# pH.net
KiCad netlist of a schematic drawn in EAGLE
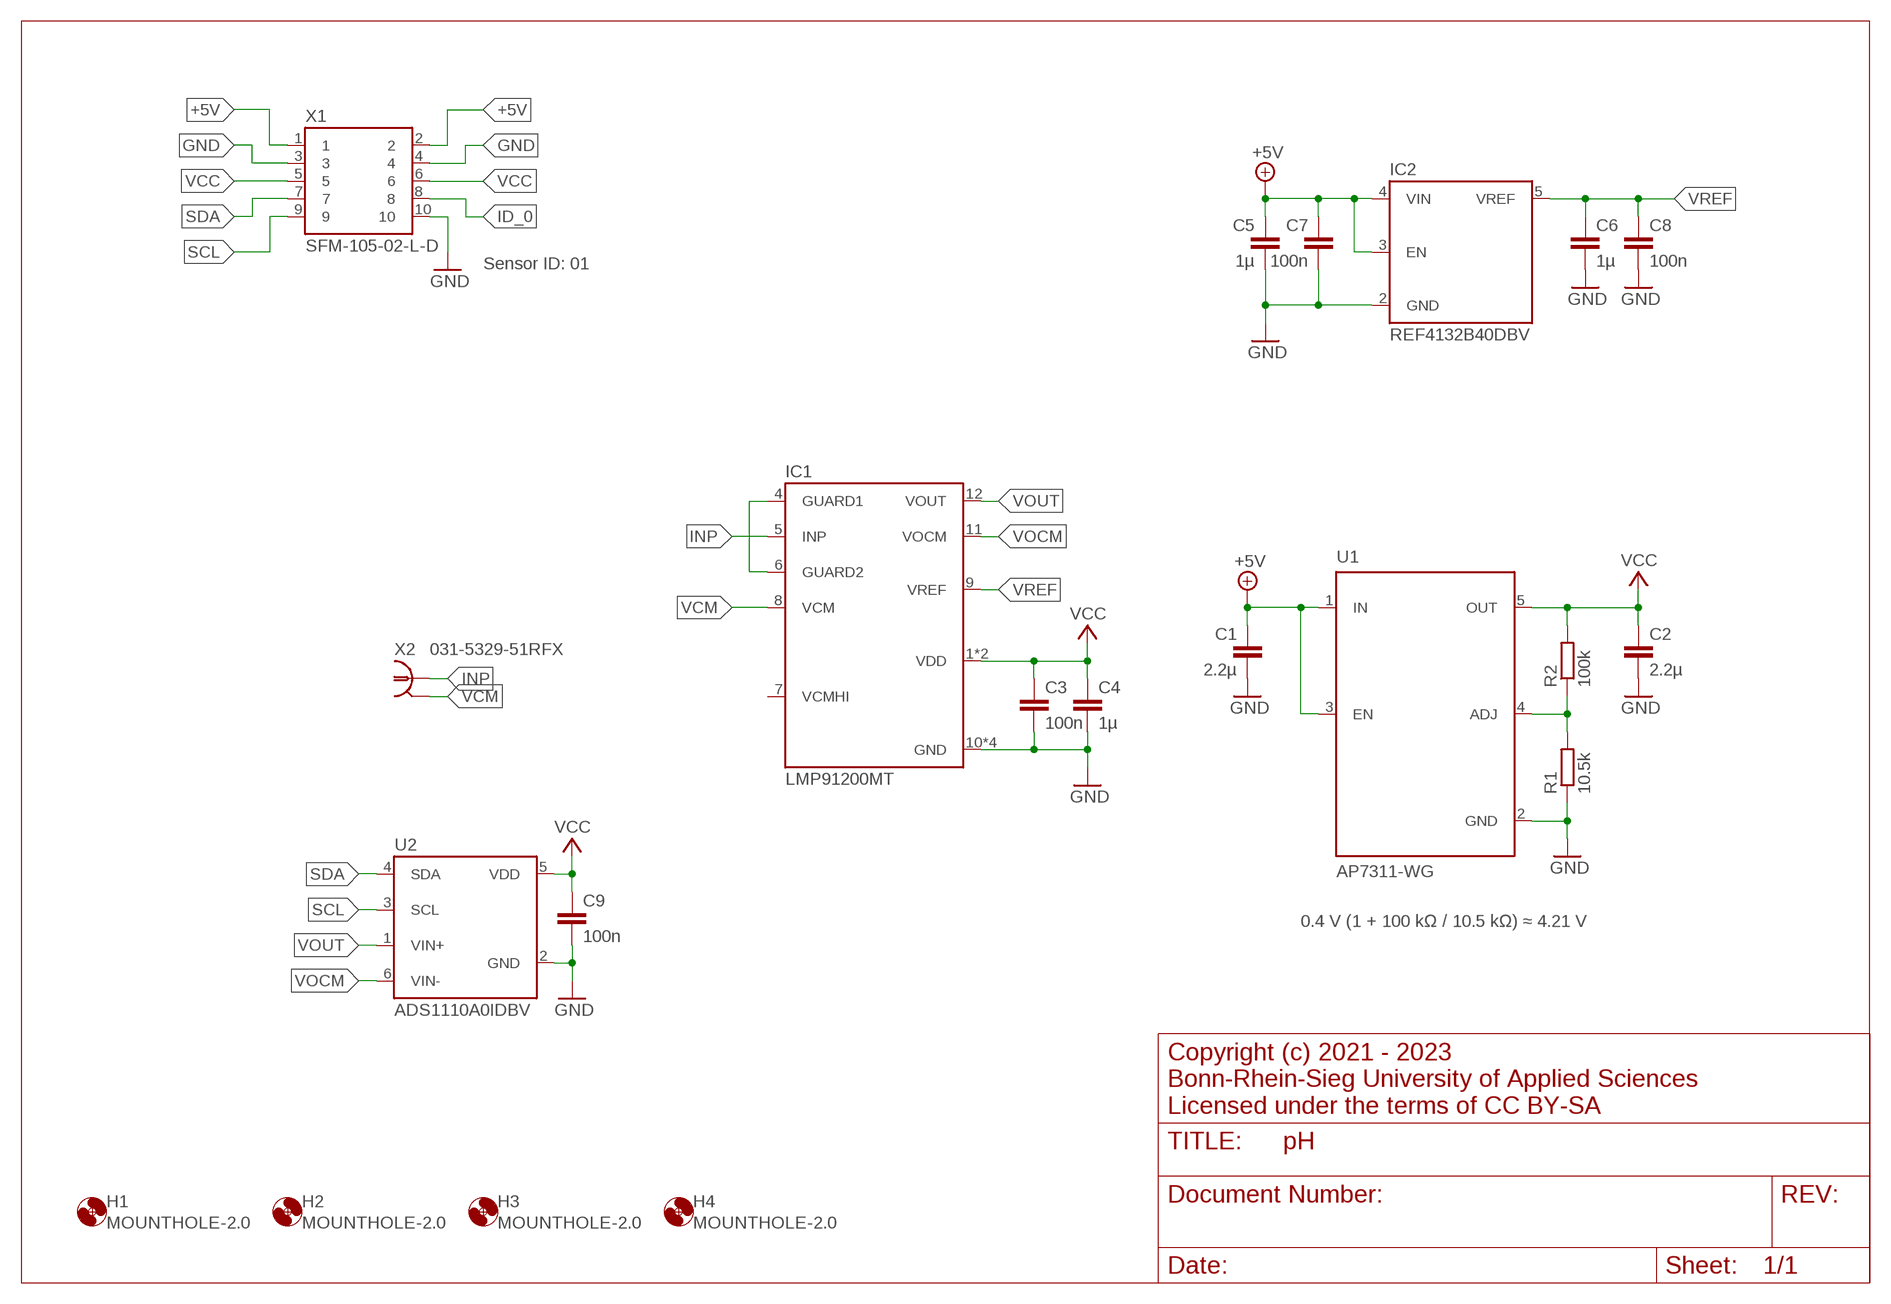
[diagram p0: schematic, sheet 1]

(export (version "E")
  (design (tool "Eeschema 10.0.6"))
  (components
    (comp (ref "C1")
      (value "2.2µ")
      (footprint "eagle-import:C0603")
      (libsource (lib "eagle-import") (part "C-EUC0603"))
    )
    (comp (ref "C2")
      (value "2.2µ")
      (footprint "eagle-import:C0603")
      (libsource (lib "eagle-import") (part "C-EUC0603"))
    )
    (comp (ref "C3")
      (value "100n")
      (footprint "eagle-import:C0603")
      (libsource (lib "eagle-import") (part "C-EUC0603"))
    )
    (comp (ref "C4")
      (value "1µ")
      (footprint "eagle-import:C0603")
      (libsource (lib "eagle-import") (part "C-EUC0603"))
    )
    (comp (ref "C5")
      (value "1µ")
      (footprint "eagle-import:C0603")
      (libsource (lib "eagle-import") (part "C-EUC0603"))
    )
    (comp (ref "C6")
      (value "1µ")
      (footprint "eagle-import:C0603")
      (libsource (lib "eagle-import") (part "C-EUC0603"))
    )
    (comp (ref "C7")
      (value "100n")
      (footprint "eagle-import:C0603")
      (libsource (lib "eagle-import") (part "C-EUC0603"))
    )
    (comp (ref "C8")
      (value "100n")
      (footprint "eagle-import:C0603")
      (libsource (lib "eagle-import") (part "C-EUC0603"))
    )
    (comp (ref "C9")
      (value "100n")
      (footprint "eagle-import:C0603")
      (libsource (lib "eagle-import") (part "C-EUC0603"))
    )
    (comp (ref "H1")
      (value "MOUNTHOLE-2.0")
      (footprint "eagle-import:2.0")
      (libsource (lib "eagle-import") (part "MOUNTHOLE-2.0"))
    )
    (comp (ref "H2")
      (value "MOUNTHOLE-2.0")
      (footprint "eagle-import:2.0")
      (libsource (lib "eagle-import") (part "MOUNTHOLE-2.0"))
    )
    (comp (ref "H3")
      (value "MOUNTHOLE-2.0")
      (footprint "eagle-import:2.0")
      (libsource (lib "eagle-import") (part "MOUNTHOLE-2.0"))
    )
    (comp (ref "H4")
      (value "MOUNTHOLE-2.0")
      (footprint "eagle-import:2.0")
      (libsource (lib "eagle-import") (part "MOUNTHOLE-2.0"))
    )
    (comp (ref "IC1")
      (value "LMP91200MT")
      (footprint "eagle-import:TSSOP16")
      (libsource (lib "eagle-import") (part "LMP91200MT"))
    )
    (comp (ref "IC2")
      (value "REF4132B40DBV")
      (footprint "eagle-import:SOT23-5")
      (libsource (lib "eagle-import") (part "REF4132DBVB40"))
    )
    (comp (ref "R1")
      (value "10.5k")
      (footprint "eagle-import:R0603")
      (libsource (lib "eagle-import") (part "R-EU_R0603"))
    )
    (comp (ref "R2")
      (value "100k")
      (footprint "eagle-import:R0603")
      (libsource (lib "eagle-import") (part "R-EU_R0603"))
    )
    (comp (ref "U1")
      (value "AP7311-WG")
      (footprint "eagle-import:SOT-23")
      (libsource (lib "eagle-import") (part "AP7311-?WG"))
    )
    (comp (ref "U2")
      (value "ADS1110A0IDBV")
      (footprint "eagle-import:SOT23-6")
      (libsource (lib "eagle-import") (part "ADS1110I?DBVA0"))
    )
    (comp (ref "X1")
      (value "SFM-105-02-L-D")
      (footprint "eagle-import:SAMTEC-SFM-105-02-L-D")
      (libsource (lib "eagle-import") (part "SFM-105-02-L-D"))
    )
    (comp (ref "X2")
      (value "031-5329-51RFX")
      (footprint "eagle-import:031-5329-51RFX")
      (libsource (lib "eagle-import") (part "031-5329-51RFX"))
    )
  )
  (nets
    (net (code "1") (name "+5V") (class "Default")
      (node (ref "C1") (pin "1") (pinfunction "1_1") (pintype "passive"))
      (node (ref "C5") (pin "1") (pinfunction "1_1") (pintype "passive"))
      (node (ref "C7") (pin "1") (pinfunction "1_1") (pintype "passive"))
      (node (ref "IC2") (pin "3") (pinfunction "EN_3") (pintype "bidirectional"))
      (node (ref "IC2") (pin "4") (pinfunction "VIN_4") (pintype "bidirectional"))
      (node (ref "U1") (pin "1") (pinfunction "IN_1") (pintype "bidirectional"))
      (node (ref "U1") (pin "3") (pinfunction "EN_3") (pintype "bidirectional"))
      (node (ref "X1") (pin "1") (pinfunction "1_1") (pintype "passive"))
      (node (ref "X1") (pin "2") (pinfunction "2_2") (pintype "passive"))
    )
    (net (code "2") (name "GND") (class "Default")
      (node (ref "C1") (pin "2") (pinfunction "2_2") (pintype "passive"))
      (node (ref "C2") (pin "2") (pinfunction "2_2") (pintype "passive"))
      (node (ref "C3") (pin "2") (pinfunction "2_2") (pintype "passive"))
      (node (ref "C4") (pin "2") (pinfunction "2_2") (pintype "passive"))
      (node (ref "C5") (pin "2") (pinfunction "2_2") (pintype "passive"))
      (node (ref "C6") (pin "2") (pinfunction "2_2") (pintype "passive"))
      (node (ref "C7") (pin "2") (pinfunction "2_2") (pintype "passive"))
      (node (ref "C8") (pin "2") (pinfunction "2_2") (pintype "passive"))
      (node (ref "C9") (pin "2") (pinfunction "2_2") (pintype "passive"))
      (node (ref "IC1") (pin "10") (pinfunction "GND_10") (pintype "bidirectional"))
      (node (ref "IC1") (pin "13") (pinfunction "GND_13") (pintype "bidirectional"))
      (node (ref "IC1") (pin "15") (pinfunction "GND_15") (pintype "bidirectional"))
      (node (ref "IC1") (pin "16") (pinfunction "GND_16") (pintype "bidirectional"))
      (node (ref "IC2") (pin "2") (pinfunction "GND_2") (pintype "bidirectional"))
      (node (ref "R1") (pin "1") (pinfunction "1_1") (pintype "passive"))
      (node (ref "U1") (pin "2") (pinfunction "GND_2") (pintype "bidirectional"))
      (node (ref "U2") (pin "2") (pinfunction "GND_2") (pintype "bidirectional"))
      (node (ref "X1") (pin "10") (pinfunction "10_10") (pintype "passive"))
      (node (ref "X1") (pin "3") (pinfunction "3_3") (pintype "passive"))
      (node (ref "X1") (pin "4") (pinfunction "4_4") (pintype "passive"))
    )
    (net (code "3") (name "ID_0") (class "Default")
      (node (ref "X1") (pin "8") (pinfunction "8_8") (pintype "passive"))
    )
    (net (code "4") (name "INP") (class "Default")
      (node (ref "IC1") (pin "5") (pinfunction "INP_5") (pintype "bidirectional"))
      (node (ref "X2") (pin "1") (pinfunction "1_1") (pintype "passive"))
    )
    (net (code "5") (name "Net-(IC1-GUARD1)") (class "Default")
      (node (ref "IC1") (pin "4") (pinfunction "GUARD1_4") (pintype "bidirectional"))
      (node (ref "IC1") (pin "6") (pinfunction "GUARD2_6") (pintype "bidirectional"))
    )
    (net (code "6") (name "Net-(U1-ADJ)") (class "Default")
      (node (ref "R1") (pin "2") (pinfunction "2_2") (pintype "passive"))
      (node (ref "R2") (pin "1") (pinfunction "1_1") (pintype "passive"))
      (node (ref "U1") (pin "4") (pinfunction "ADJ_4") (pintype "bidirectional"))
    )
    (net (code "7") (name "SCL") (class "Default")
      (node (ref "U2") (pin "3") (pinfunction "SCL_3") (pintype "bidirectional"))
      (node (ref "X1") (pin "9") (pinfunction "9_9") (pintype "passive"))
    )
    (net (code "8") (name "SDA") (class "Default")
      (node (ref "U2") (pin "4") (pinfunction "SDA_4") (pintype "bidirectional"))
      (node (ref "X1") (pin "7") (pinfunction "7_7") (pintype "passive"))
    )
    (net (code "9") (name "VCC") (class "Default")
      (node (ref "C2") (pin "1") (pinfunction "1_1") (pintype "passive"))
      (node (ref "C3") (pin "1") (pinfunction "1_1") (pintype "passive"))
      (node (ref "C4") (pin "1") (pinfunction "1_1") (pintype "passive"))
      (node (ref "C9") (pin "1") (pinfunction "1_1") (pintype "passive"))
      (node (ref "IC1") (pin "1") (pinfunction "VDD_1") (pintype "bidirectional"))
      (node (ref "IC1") (pin "14") (pinfunction "VDD_14") (pintype "bidirectional"))
      (node (ref "R2") (pin "2") (pinfunction "2_2") (pintype "passive"))
      (node (ref "U1") (pin "5") (pinfunction "OUT_5") (pintype "bidirectional"))
      (node (ref "U2") (pin "5") (pinfunction "VDD_5") (pintype "bidirectional"))
      (node (ref "X1") (pin "5") (pinfunction "5_5") (pintype "passive"))
      (node (ref "X1") (pin "6") (pinfunction "6_6") (pintype "passive"))
    )
    (net (code "10") (name "VCM") (class "Default")
      (node (ref "IC1") (pin "8") (pinfunction "VCM_8") (pintype "bidirectional"))
      (node (ref "X2") (pin "2") (pinfunction "2_2") (pintype "passive"))
      (node (ref "X2") (pin "3") (pinfunction "2_3") (pintype "passive"))
      (node (ref "X2") (pin "4") (pinfunction "2_4") (pintype "passive"))
      (node (ref "X2") (pin "5") (pinfunction "2_5") (pintype "passive"))
    )
    (net (code "11") (name "VOCM") (class "Default")
      (node (ref "IC1") (pin "11") (pinfunction "VOCM_11") (pintype "bidirectional"))
      (node (ref "U2") (pin "6") (pinfunction "VIN-_6") (pintype "bidirectional"))
    )
    (net (code "12") (name "VOUT") (class "Default")
      (node (ref "IC1") (pin "12") (pinfunction "VOUT_12") (pintype "bidirectional"))
      (node (ref "U2") (pin "1") (pinfunction "VIN+_1") (pintype "bidirectional"))
    )
    (net (code "13") (name "VREF") (class "Default")
      (node (ref "C6") (pin "1") (pinfunction "1_1") (pintype "passive"))
      (node (ref "C8") (pin "1") (pinfunction "1_1") (pintype "passive"))
      (node (ref "IC1") (pin "9") (pinfunction "VREF_9") (pintype "bidirectional"))
      (node (ref "IC2") (pin "5") (pinfunction "VREF_5") (pintype "bidirectional"))
    )
    (net (code "14") (name "unconnected-(IC1-VCMHI-Pad7)") (class "Default")
      (node (ref "IC1") (pin "7") (pinfunction "VCMHI_7") (pintype "bidirectional"))
    )
  )
)
